# WIFI_MODULE.net
KiCad netlist of a schematic drawn in Altium Designer
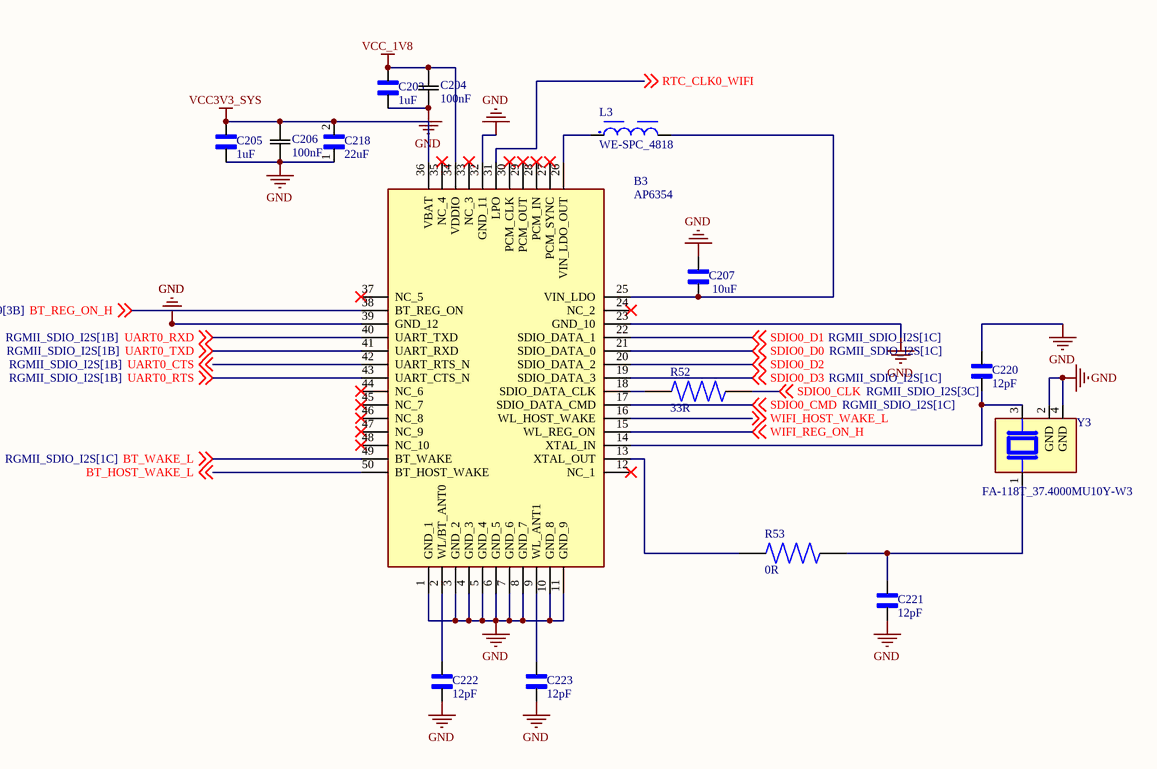
[diagram p0: WIFI_MODULE.SchDoc]

(export (version "E")
  (design (tool "Eeschema 10.0.6"))
  (components
    (comp (ref "B3")
      (value "AP6354")
      (footprint "AP6354")
      (description "CON")
      (libsource (lib "AP6354") (part "AP6354"))
    )
    (comp (ref "C203")
      (value "1uF")
      (footprint "CAPC1005X56N")
      (description "1 ÂµF Â±10% 10V Ceramic Capacitor X5R 0402 (1005 Metric)")
      (fields (field (name "MF") "AVX") (field (name "MP") "0402ZD105KAT4A"))
      (libsource (lib "0402ZD105KAT4A") (part "0402ZD105KAT4A"))
    )
    (comp (ref "C204")
      (value "100nF")
      (footprint "CAP_1005_TDK")
      (description "Description")
      (fields
        (field (name "MANUFACTURER_PART_NUMBER") "C1005X7R1H104M050BB")
        (field (name "COPYRIGHT") "Copyright (C) 2025 Ultra Librarian. All rights reserved.")
      )
      (libsource (lib "C1005X7R1H104M050BB") (part "C1005X7R1H104M050BB"))
    )
    (comp (ref "C205")
      (value "1uF")
      (footprint "CAPC1005X56N")
      (description "1 ÂµF Â±10% 10V Ceramic Capacitor X5R 0402 (1005 Metric)")
      (fields (field (name "MF") "AVX") (field (name "MP") "0402ZD105KAT4A"))
      (libsource (lib "0402ZD105KAT4A") (part "0402ZD105KAT4A"))
    )
    (comp (ref "C206")
      (value "100nF")
      (footprint "CAP_1005_TDK")
      (description "Description")
      (fields
        (field (name "MANUFACTURER_PART_NUMBER") "C1005X7R1H104M050BB")
        (field (name "COPYRIGHT") "Copyright (C) 2025 Ultra Librarian. All rights reserved.")
      )
      (libsource (lib "C1005X7R1H104M050BB") (part "C1005X7R1H104M050BB"))
    )
    (comp (ref "C207")
      (value "10uF")
      (footprint "CAPC1005X70N")
      (description "10 ÂµF Â±20% 6.3V Ceramic Capacitor X5R 0402 (1005 Metric)")
      (fields (field (name "MF") "Samsung") (field (name "MP") "CL05A106MQ5NUNC"))
      (libsource (lib "CL05A106MQ5NUNC") (part "CL05A106MQ5NUNC"))
    )
    (comp (ref "C218")
      (value "22uF")
      (footprint "CAPC6050X550N")
      (description "22ÂµF Â±20% 50V Ceramic Capacitor X7S Stacked SMD, 2 J-Lead")
      (fields (field (name "MP") "CKG57NX7S1H226M500JJ"))
      (libsource (lib "CKG57NX7S1H226M500JJ") (part "CKG57NX7S1H226M500JJ"))
    )
    (comp (ref "C220")
      (value "12pF")
      (footprint "CAPC1608X90")
      (description "12 pF Thin Film Capacitor 50 V 0603 (1608 Metric)")
      (fields (field (name "MF") "AVX") (field (name "MP") "06035J120FBSTR"))
      (libsource (lib "") (part "06035J120FBSTR_1"))
    )
    (comp (ref "C221")
      (value "12pF")
      (footprint "CAPC1608X90")
      (description "12 pF Thin Film Capacitor 50 V 0603 (1608 Metric)")
      (fields (field (name "MF") "AVX") (field (name "MP") "06035J120FBSTR"))
      (libsource (lib "") (part "06035J120FBSTR_1"))
    )
    (comp (ref "C222")
      (value "12pF")
      (footprint "CAPC1608X90")
      (description "12 pF Thin Film Capacitor 50 V 0603 (1608 Metric)")
      (fields (field (name "MF") "AVX") (field (name "MP") "06035J120FBSTR"))
      (libsource (lib "06035J120FBSTR") (part "06035J120FBSTR"))
    )
    (comp (ref "C223")
      (value "12pF")
      (footprint "CAPC1608X90")
      (description "12 pF Thin Film Capacitor 50 V 0603 (1608 Metric)")
      (fields (field (name "MF") "AVX") (field (name "MP") "06035J120FBSTR"))
      (libsource (lib "06035J120FBSTR") (part "06035J120FBSTR"))
    )
    (comp (ref "L3")
      (value "WE-SPC_4818")
      (footprint "WE-SPC_4818")
      (description "10 ÂµH Shielded Drum Core, Wirewound Inductor 900 mA 248mOhm Max 1919 (4848 Metric)")
      (fields (field (name "MF") "WÃ¼rth Elektronik") (field (name "MP") "74408941100"))
      (libsource (lib "WE-SPC_4818") (part "WE-SPC_4818"))
    )
    (comp (ref "R52")
      (value "33R")
      (footprint "RES_ERA6AHD330V")
      (fields (field (name "MP") "ERA6AHD330V"))
      (libsource (lib "ERA6AHD330V") (part "ERA6AHD330V"))
    )
    (comp (ref "R53")
      (value "0R")
      (footprint "RES_ERJH6G0R00V")
      (fields (field (name "MP") "ERJH6G0R00V"))
      (libsource (lib "ERJH6G0R00V") (part "ERJH6G0R00V"))
    )
    (comp (ref "Y3")
      (value "FA-118T_37.4000MU10Y-W3")
      (footprint "XTAL_FA-118T_37.4000MU10Y-W3")
      (description "Crystals XTL MHZ +/-7PPM+/-10PPM-30 85C 12PF ESR=60 OHM 250TR")
      (fields (field (name "MF") "EPSON") (field (name "MP") "FA-118T 37.4000MU10Y-W3"))
      (libsource (lib "FA-118T_37.4000MU10Y-W3") (part "FA-118T_37.4000MU10Y-W3"))
    )
  )
  (nets
    (net (code "1") (name "BT_HOST_WAKE_L") (class "Default")
      (node (ref "B3") (pin "50") (pinfunction "BT_HOST_WAKE_50") (pintype "passive"))
    )
    (net (code "2") (name "BT_REG_ON_H") (class "Default")
      (node (ref "B3") (pin "38") (pinfunction "BT_REG_ON_38") (pintype "passive"))
    )
    (net (code "3") (name "BT_WAKE_L") (class "Default")
      (node (ref "B3") (pin "49") (pinfunction "BT_WAKE_49") (pintype "passive"))
    )
    (net (code "4") (name "GND") (class "Default")
      (node (ref "B3") (pin "1") (pinfunction "GND_1_1") (pintype "passive"))
      (node (ref "B3") (pin "10") (pinfunction "GND_8_10") (pintype "passive"))
      (node (ref "B3") (pin "11") (pinfunction "GND_9_11") (pintype "passive"))
      (node (ref "B3") (pin "23") (pinfunction "GND_10_23") (pintype "passive"))
      (node (ref "B3") (pin "3") (pinfunction "GND_2_3") (pintype "passive"))
      (node (ref "B3") (pin "32") (pinfunction "GND_11_32") (pintype "passive"))
      (node (ref "B3") (pin "39") (pinfunction "GND_12_39") (pintype "passive"))
      (node (ref "B3") (pin "4") (pinfunction "GND_3_4") (pintype "passive"))
      (node (ref "B3") (pin "5") (pinfunction "GND_4_5") (pintype "passive"))
      (node (ref "B3") (pin "6") (pinfunction "GND_5_6") (pintype "passive"))
      (node (ref "B3") (pin "7") (pinfunction "GND_6_7") (pintype "passive"))
      (node (ref "B3") (pin "8") (pinfunction "GND_7_8") (pintype "passive"))
      (node (ref "C203") (pin "1") (pinfunction "1_1") (pintype "passive"))
      (node (ref "C204") (pin "1") (pinfunction "1_1") (pintype "passive"))
      (node (ref "C205") (pin "1") (pinfunction "1_1") (pintype "passive"))
      (node (ref "C206") (pin "1") (pinfunction "1_1") (pintype "passive"))
      (node (ref "C207") (pin "2") (pinfunction "2_2") (pintype "passive"))
      (node (ref "C218") (pin "1") (pinfunction "1_1") (pintype "passive"))
      (node (ref "C220") (pin "2") (pinfunction "2_2") (pintype "passive"))
      (node (ref "C221") (pin "1") (pinfunction "1_1") (pintype "passive"))
      (node (ref "C222") (pin "2") (pinfunction "2_2") (pintype "passive"))
      (node (ref "C223") (pin "2") (pinfunction "2_2") (pintype "passive"))
      (node (ref "Y3") (pin "2") (pinfunction "GND_2") (pintype "power_in"))
      (node (ref "Y3") (pin "4") (pinfunction "GND_4") (pintype "power_in"))
    )
    (net (code "5") (name "Net-(B3-SDIO_DATA_CLK)") (class "Default")
      (node (ref "B3") (pin "18") (pinfunction "SDIO_DATA_CLK_18") (pintype "passive"))
      (node (ref "R52") (pin "1") (pinfunction "1_1") (pintype "passive"))
    )
    (net (code "6") (name "Net-(B3-VIN_LDO)") (class "Default")
      (node (ref "B3") (pin "25") (pinfunction "VIN_LDO_25") (pintype "passive"))
      (node (ref "C207") (pin "1") (pinfunction "1_1") (pintype "passive"))
      (node (ref "L3") (pin "2") (pinfunction "2_2") (pintype "passive"))
    )
    (net (code "7") (name "Net-(B3-VIN_LDO_OUT)") (class "Default")
      (node (ref "B3") (pin "26") (pinfunction "VIN_LDO_OUT_26") (pintype "passive"))
      (node (ref "L3") (pin "1") (pinfunction "1_1") (pintype "passive"))
    )
    (net (code "8") (name "Net-(B3-WL_ANT1)") (class "Default")
      (node (ref "B3") (pin "9") (pinfunction "WL_ANT1_9") (pintype "passive"))
      (node (ref "C223") (pin "1") (pinfunction "1_1") (pintype "passive"))
    )
    (net (code "9") (name "Net-(B3-WL{slash}BT_ANT0)") (class "Default")
      (node (ref "B3") (pin "2") (pinfunction "WL/BT_ANT0_2") (pintype "passive"))
      (node (ref "C222") (pin "1") (pinfunction "1_1") (pintype "passive"))
    )
    (net (code "10") (name "Net-(B3-XTAL_IN)") (class "Default")
      (node (ref "B3") (pin "14") (pinfunction "XTAL_IN_14") (pintype "passive"))
      (node (ref "C220") (pin "1") (pinfunction "1_1") (pintype "passive"))
      (node (ref "Y3") (pin "3") (pinfunction "2_3") (pintype "passive"))
    )
    (net (code "11") (name "Net-(B3-XTAL_OUT)") (class "Default")
      (node (ref "B3") (pin "13") (pinfunction "XTAL_OUT_13") (pintype "passive"))
      (node (ref "R53") (pin "1") (pinfunction "1_1") (pintype "passive"))
    )
    (net (code "12") (name "Net-(C221-Pad2)") (class "Default")
      (node (ref "C221") (pin "2") (pinfunction "2_2") (pintype "passive"))
      (node (ref "R53") (pin "2") (pinfunction "2_2") (pintype "passive"))
      (node (ref "Y3") (pin "1") (pinfunction "1_1") (pintype "passive"))
    )
    (net (code "13") (name "RTC_CLK0_WIFI") (class "Default")
      (node (ref "B3") (pin "31") (pinfunction "LPO_31") (pintype "passive"))
    )
    (net (code "14") (name "SDIO0_CLK") (class "Default")
      (node (ref "R52") (pin "2") (pinfunction "2_2") (pintype "passive"))
    )
    (net (code "15") (name "SDIO0_CMD") (class "Default")
      (node (ref "B3") (pin "17") (pinfunction "SDIO_DATA_CMD_17") (pintype "passive"))
    )
    (net (code "16") (name "SDIO0_D0") (class "Default")
      (node (ref "B3") (pin "21") (pinfunction "SDIO_DATA_0_21") (pintype "passive"))
    )
    (net (code "17") (name "SDIO0_D1") (class "Default")
      (node (ref "B3") (pin "22") (pinfunction "SDIO_DATA_1_22") (pintype "passive"))
    )
    (net (code "18") (name "SDIO0_D2") (class "Default")
      (node (ref "B3") (pin "20") (pinfunction "SDIO_DATA_2_20") (pintype "passive"))
    )
    (net (code "19") (name "SDIO0_D3") (class "Default")
      (node (ref "B3") (pin "19") (pinfunction "SDIO_DATA_3_19") (pintype "passive"))
    )
    (net (code "20") (name "UART0_CTS") (class "Default")
      (node (ref "B3") (pin "42") (pinfunction "UART_RTS_N_42") (pintype "passive"))
    )
    (net (code "21") (name "UART0_RTS") (class "Default")
      (node (ref "B3") (pin "43") (pinfunction "UART_CTS_N_43") (pintype "passive"))
    )
    (net (code "22") (name "UART0_RXD") (class "Default")
      (node (ref "B3") (pin "40") (pinfunction "UART_TXD_40") (pintype "passive"))
    )
    (net (code "23") (name "UART0_TXD") (class "Default")
      (node (ref "B3") (pin "41") (pinfunction "UART_RXD_41") (pintype "passive"))
    )
    (net (code "24") (name "VCC3V3_SYS") (class "Default")
      (node (ref "B3") (pin "36") (pinfunction "VBAT_36") (pintype "passive"))
      (node (ref "C205") (pin "2") (pinfunction "2_2") (pintype "passive"))
      (node (ref "C206") (pin "2") (pinfunction "2_2") (pintype "passive"))
      (node (ref "C218") (pin "2") (pinfunction "2_2") (pintype "passive"))
    )
    (net (code "25") (name "VCC_1V8") (class "Default")
      (node (ref "B3") (pin "34") (pinfunction "VDDIO_34") (pintype "passive"))
      (node (ref "C203") (pin "2") (pinfunction "2_2") (pintype "passive"))
      (node (ref "C204") (pin "2") (pinfunction "2_2") (pintype "passive"))
    )
    (net (code "26") (name "WIFI_HOST_WAKE_L") (class "Default")
      (node (ref "B3") (pin "16") (pinfunction "WL_HOST_WAKE_16") (pintype "passive"))
    )
    (net (code "27") (name "WIFI_REG_ON_H") (class "Default")
      (node (ref "B3") (pin "15") (pinfunction "WL_REG_ON_15") (pintype "passive"))
    )
    (net (code "28") (name "unconnected-(B3-NC_1-Pad12)") (class "Default")
      (node (ref "B3") (pin "12") (pinfunction "NC_1_12") (pintype "passive+no_connect"))
    )
    (net (code "29") (name "unconnected-(B3-NC_2-Pad24)") (class "Default")
      (node (ref "B3") (pin "24") (pinfunction "NC_2_24") (pintype "passive+no_connect"))
    )
    (net (code "30") (name "unconnected-(B3-NC_3-Pad33)") (class "Default")
      (node (ref "B3") (pin "33") (pinfunction "NC_3_33") (pintype "passive+no_connect"))
    )
    (net (code "31") (name "unconnected-(B3-NC_4-Pad35)") (class "Default")
      (node (ref "B3") (pin "35") (pinfunction "NC_4_35") (pintype "passive+no_connect"))
    )
    (net (code "32") (name "unconnected-(B3-NC_5-Pad37)") (class "Default")
      (node (ref "B3") (pin "37") (pinfunction "NC_5_37") (pintype "passive+no_connect"))
    )
    (net (code "33") (name "unconnected-(B3-NC_6-Pad44)") (class "Default")
      (node (ref "B3") (pin "44") (pinfunction "NC_6_44") (pintype "passive+no_connect"))
    )
    (net (code "34") (name "unconnected-(B3-NC_7-Pad45)") (class "Default")
      (node (ref "B3") (pin "45") (pinfunction "NC_7_45") (pintype "passive+no_connect"))
    )
    (net (code "35") (name "unconnected-(B3-NC_8-Pad46)") (class "Default")
      (node (ref "B3") (pin "46") (pinfunction "NC_8_46") (pintype "passive+no_connect"))
    )
    (net (code "36") (name "unconnected-(B3-NC_9-Pad47)") (class "Default")
      (node (ref "B3") (pin "47") (pinfunction "NC_9_47") (pintype "passive+no_connect"))
    )
    (net (code "37") (name "unconnected-(B3-NC_10-Pad48)") (class "Default")
      (node (ref "B3") (pin "48") (pinfunction "NC_10_48") (pintype "passive+no_connect"))
    )
    (net (code "38") (name "unconnected-(B3-PCM_CLK-Pad30)") (class "Default")
      (node (ref "B3") (pin "30") (pinfunction "PCM_CLK_30") (pintype "passive+no_connect"))
    )
    (net (code "39") (name "unconnected-(B3-PCM_IN-Pad28)") (class "Default")
      (node (ref "B3") (pin "28") (pinfunction "PCM_IN_28") (pintype "passive+no_connect"))
    )
    (net (code "40") (name "unconnected-(B3-PCM_OUT-Pad29)") (class "Default")
      (node (ref "B3") (pin "29") (pinfunction "PCM_OUT_29") (pintype "passive+no_connect"))
    )
    (net (code "41") (name "unconnected-(B3-PCM_SYNC-Pad27)") (class "Default")
      (node (ref "B3") (pin "27") (pinfunction "PCM_SYNC_27") (pintype "passive+no_connect"))
    )
  )
)
